# GPIO_EXT.net
KiCad netlist of a schematic drawn in Altium Designer
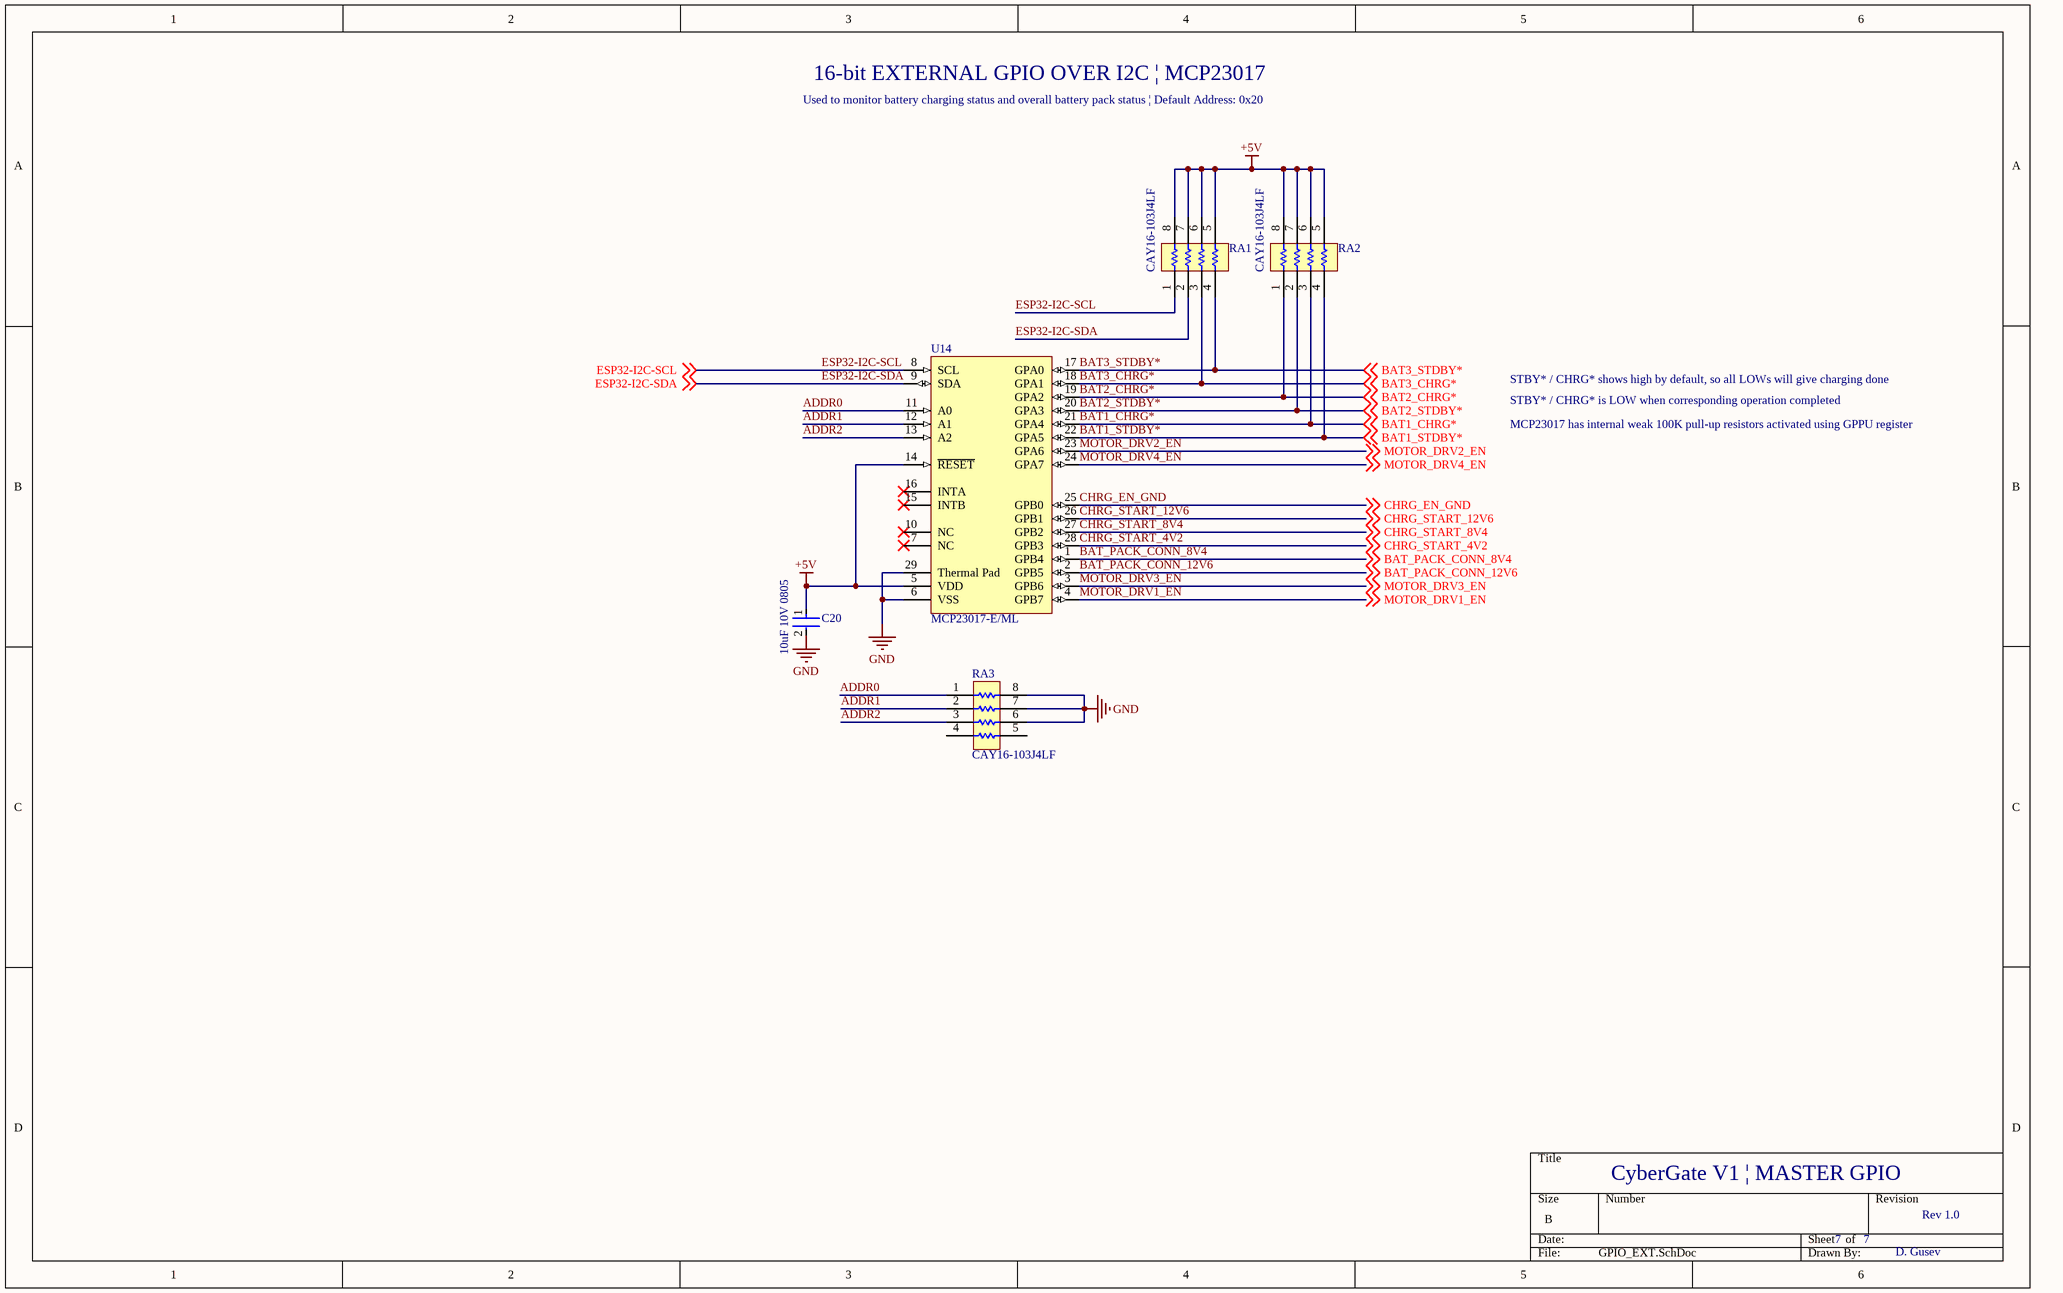
[diagram p0: GPIO_EXT.SchDoc]

(export (version "E")
  (design (tool "Eeschema 10.0.6"))
  (components
    (comp (ref "C20")
      (value "10uF 10V 0805")
      (footprint "FP-C0805C-DG-MFG")
      (description "CAP CER 10UF 10V X5R 0805")
      (fields (field (name "TOLERANCE") "10%") (field (name "MANUFACTURER PART NUMBER") "C0805C106K8PACTU"))
      (libsource (lib "Altium Content Vault") (part "11868f565c42a9108669ba33697ecf6"))
    )
    (comp (ref "RA1")
      (value "CAY16-103J4LF")
      (footprint "BOUR-CAY16-J4_V")
      (description "Chip Resistor Array, 10 KOhm, +/- 5%, 62.5 mW, -55 to 125 degC, 8-Pin SMD, RoHS, Tape and Reel")
      (fields (field (name "TOLERANCE") "1%"))
      (libsource (lib "Altium Content Vault") (part "RES-P-8"))
    )
    (comp (ref "RA2")
      (value "CAY16-103J4LF")
      (footprint "BOUR-CAY16-J4_V")
      (description "Chip Resistor Array, 10 KOhm, +/- 5%, 62.5 mW, -55 to 125 degC, 8-Pin SMD, RoHS, Tape and Reel")
      (fields (field (name "TOLERANCE") "1%"))
      (libsource (lib "Altium Content Vault") (part "RES-P-8"))
    )
    (comp (ref "RA3")
      (value "CAY16-103J4LF")
      (footprint "BOUR-CAY16-J4_V")
      (description "Chip Resistor Array, 10 KOhm, +/- 5%, 62.5 mW, -55 to 125 degC, 8-Pin SMD, RoHS, Tape and Reel")
      (fields (field (name "TOLERANCE") "1%"))
      (libsource (lib "") (part "RES-P-8_1"))
    )
    (comp (ref "U14")
      (value "MCP23017-E/ML")
      (footprint "MCP23017")
      (description "16-Bit I/O Expander with Serial Interface, 28-Pin QFN, Extended Temperature")
      (libsource (lib "ddrlegobrick") (part "MCP23017"))
    )
  )
  (nets
    (net (code "1") (name "+5V") (class "Default")
      (node (ref "C20") (pin "1") (pinfunction "1_1") (pintype "passive"))
      (node (ref "RA1") (pin "5") (pinfunction "5_5") (pintype "passive"))
      (node (ref "RA1") (pin "6") (pinfunction "6_6") (pintype "passive"))
      (node (ref "RA1") (pin "7") (pinfunction "7_7") (pintype "passive"))
      (node (ref "RA1") (pin "8") (pinfunction "8_8") (pintype "passive"))
      (node (ref "RA2") (pin "5") (pinfunction "5_5") (pintype "passive"))
      (node (ref "RA2") (pin "6") (pinfunction "6_6") (pintype "passive"))
      (node (ref "RA2") (pin "7") (pinfunction "7_7") (pintype "passive"))
      (node (ref "RA2") (pin "8") (pinfunction "8_8") (pintype "passive"))
      (node (ref "U14") (pin "14") (pinfunction "~{RESET}_14") (pintype "input"))
      (node (ref "U14") (pin "5") (pinfunction "VDD_5") (pintype "power_in"))
    )
    (net (code "2") (name "/ADDR0") (class "Default")
      (node (ref "RA3") (pin "1") (pinfunction "1_1") (pintype "passive"))
      (node (ref "U14") (pin "11") (pinfunction "A0_11") (pintype "input"))
    )
    (net (code "3") (name "/ADDR1") (class "Default")
      (node (ref "RA3") (pin "2") (pinfunction "2_2") (pintype "passive"))
      (node (ref "U14") (pin "12") (pinfunction "A1_12") (pintype "input"))
    )
    (net (code "4") (name "/ADDR2") (class "Default")
      (node (ref "RA3") (pin "3") (pinfunction "3_3") (pintype "passive"))
      (node (ref "U14") (pin "13") (pinfunction "A2_13") (pintype "input"))
    )
    (net (code "5") (name "BAT1_CHRG*") (class "Default")
      (node (ref "RA2") (pin "3") (pinfunction "3_3") (pintype "passive"))
      (node (ref "U14") (pin "21") (pinfunction "GPA4_21") (pintype "bidirectional"))
    )
    (net (code "6") (name "BAT1_STDBY*") (class "Default")
      (node (ref "RA2") (pin "4") (pinfunction "4_4") (pintype "passive"))
      (node (ref "U14") (pin "22") (pinfunction "GPA5_22") (pintype "bidirectional"))
    )
    (net (code "7") (name "BAT2_CHRG*") (class "Default")
      (node (ref "RA2") (pin "1") (pinfunction "1_1") (pintype "passive"))
      (node (ref "U14") (pin "19") (pinfunction "GPA2_19") (pintype "bidirectional"))
    )
    (net (code "8") (name "BAT2_STDBY*") (class "Default")
      (node (ref "RA2") (pin "2") (pinfunction "2_2") (pintype "passive"))
      (node (ref "U14") (pin "20") (pinfunction "GPA3_20") (pintype "bidirectional"))
    )
    (net (code "9") (name "BAT3_CHRG*") (class "Default")
      (node (ref "RA1") (pin "3") (pinfunction "3_3") (pintype "passive"))
      (node (ref "U14") (pin "18") (pinfunction "GPA1_18") (pintype "bidirectional"))
    )
    (net (code "10") (name "BAT3_STDBY*") (class "Default")
      (node (ref "RA1") (pin "4") (pinfunction "4_4") (pintype "passive"))
      (node (ref "U14") (pin "17") (pinfunction "GPA0_17") (pintype "bidirectional"))
    )
    (net (code "11") (name "BAT_PACK_CONN_8V4") (class "Default")
      (node (ref "U14") (pin "1") (pinfunction "GPB4_1") (pintype "bidirectional"))
    )
    (net (code "12") (name "BAT_PACK_CONN_12V6") (class "Default")
      (node (ref "U14") (pin "2") (pinfunction "GPB5_2") (pintype "bidirectional"))
    )
    (net (code "13") (name "CHRG_EN_GND") (class "Default")
      (node (ref "U14") (pin "25") (pinfunction "GPB0_25") (pintype "bidirectional"))
    )
    (net (code "14") (name "CHRG_START_4V2") (class "Default")
      (node (ref "U14") (pin "28") (pinfunction "GPB3_28") (pintype "bidirectional"))
    )
    (net (code "15") (name "CHRG_START_8V4") (class "Default")
      (node (ref "U14") (pin "27") (pinfunction "GPB2_27") (pintype "bidirectional"))
    )
    (net (code "16") (name "CHRG_START_12V6") (class "Default")
      (node (ref "U14") (pin "26") (pinfunction "GPB1_26") (pintype "bidirectional"))
    )
    (net (code "17") (name "ESP32-I2C-SCL") (class "Default")
      (node (ref "RA1") (pin "1") (pinfunction "1_1") (pintype "passive"))
      (node (ref "U14") (pin "8") (pinfunction "SCL_8") (pintype "input"))
    )
    (net (code "18") (name "ESP32-I2C-SDA") (class "Default")
      (node (ref "RA1") (pin "2") (pinfunction "2_2") (pintype "passive"))
      (node (ref "U14") (pin "9") (pinfunction "SDA_9") (pintype "bidirectional"))
    )
    (net (code "19") (name "GND") (class "Default")
      (node (ref "C20") (pin "2") (pinfunction "2_2") (pintype "passive"))
      (node (ref "RA3") (pin "6") (pinfunction "6_6") (pintype "passive"))
      (node (ref "RA3") (pin "7") (pinfunction "7_7") (pintype "passive"))
      (node (ref "RA3") (pin "8") (pinfunction "8_8") (pintype "passive"))
      (node (ref "U14") (pin "29") (pinfunction "Thermal_Pad_29") (pintype "passive"))
      (node (ref "U14") (pin "6") (pinfunction "VSS_6") (pintype "power_in"))
    )
    (net (code "20") (name "MOTOR_DRV1_EN") (class "Default")
      (node (ref "U14") (pin "4") (pinfunction "GPB7_4") (pintype "bidirectional"))
    )
    (net (code "21") (name "MOTOR_DRV2_EN") (class "Default")
      (node (ref "U14") (pin "23") (pinfunction "GPA6_23") (pintype "bidirectional"))
    )
    (net (code "22") (name "MOTOR_DRV3_EN") (class "Default")
      (node (ref "U14") (pin "3") (pinfunction "GPB6_3") (pintype "bidirectional"))
    )
    (net (code "23") (name "MOTOR_DRV4_EN") (class "Default")
      (node (ref "U14") (pin "24") (pinfunction "GPA7_24") (pintype "bidirectional"))
    )
    (net (code "24") (name "unconnected-(RA3-Pad4)") (class "Default")
      (node (ref "RA3") (pin "4") (pinfunction "4_4") (pintype "passive"))
    )
    (net (code "25") (name "unconnected-(RA3-Pad5)") (class "Default")
      (node (ref "RA3") (pin "5") (pinfunction "5_5") (pintype "passive"))
    )
    (net (code "26") (name "unconnected-(U14-INTA-Pad16)") (class "Default")
      (node (ref "U14") (pin "16") (pinfunction "INTA_16") (pintype "open_collector+no_connect"))
    )
    (net (code "27") (name "unconnected-(U14-INTB-Pad15)") (class "Default")
      (node (ref "U14") (pin "15") (pinfunction "INTB_15") (pintype "open_collector+no_connect"))
    )
    (net (code "28") (name "unconnected-(U14-NC-Pad7)") (class "Default")
      (node (ref "U14") (pin "7") (pinfunction "NC_7") (pintype "passive+no_connect"))
    )
    (net (code "29") (name "unconnected-(U14-NC-Pad10)") (class "Default")
      (node (ref "U14") (pin "10") (pinfunction "NC_10") (pintype "passive+no_connect"))
    )
  )
)
